# MezzanineConnectors.net
KiCad netlist of a schematic drawn in Altium Designer
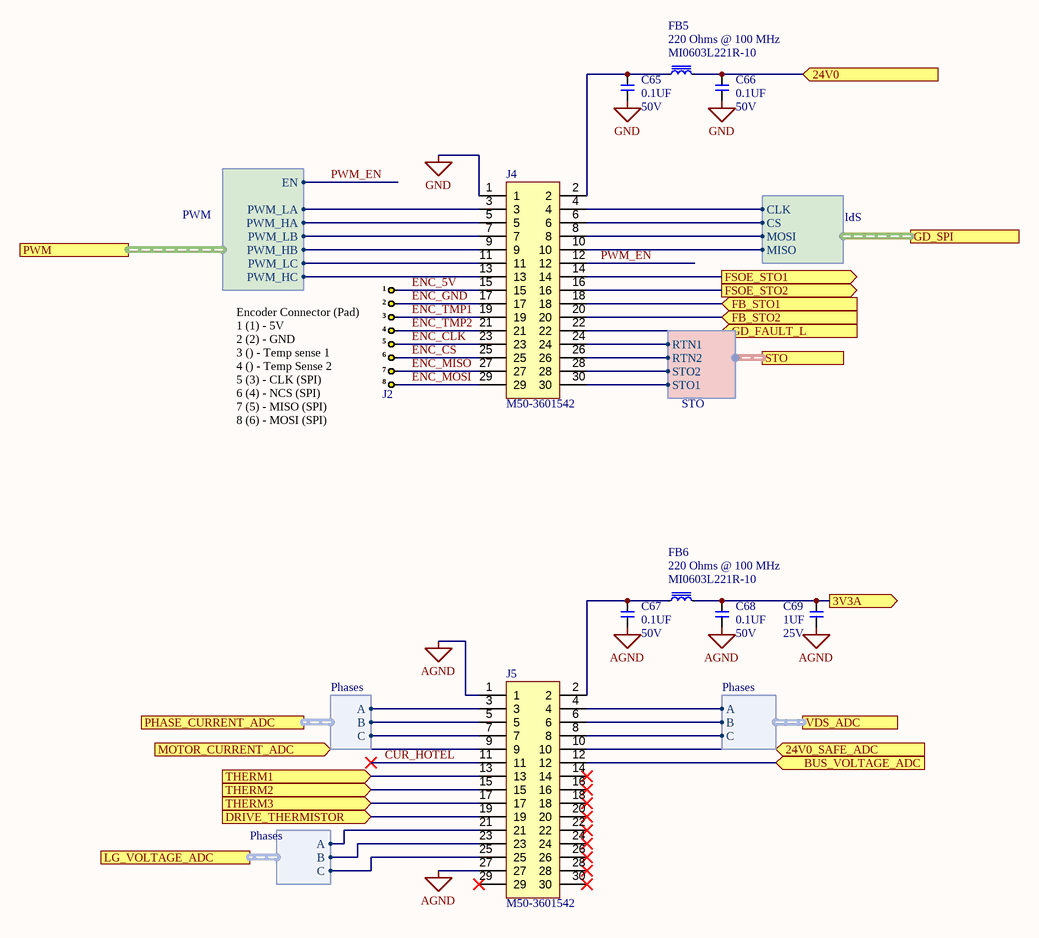
[diagram p0: MezzanineConnectors.SchDoc]

(export (version "E")
  (design (tool "Eeschema 10.0.6"))
  (components
    (comp (ref "C65")
      (value "0.1UF")
      (footprint "C0402")
      (description "CAP, CER, X5R, 0.1uF, 10%, 50V, 0402, 0.55mm")
      (fields (field (name "MFG") "YAGEO") (field (name "VOLTAGE") "50V") (field (name "TOLERANCE") "10%"))
      (libsource (lib "AltiumReleaseLibDB") (part "__Template_Cap"))
    )
    (comp (ref "C66")
      (value "0.1UF")
      (footprint "C0402")
      (description "CAP, CER, X5R, 0.1uF, 10%, 50V, 0402, 0.55mm")
      (fields (field (name "MFG") "YAGEO") (field (name "VOLTAGE") "50V") (field (name "TOLERANCE") "10%"))
      (libsource (lib "AltiumReleaseLibDB") (part "__Template_Cap"))
    )
    (comp (ref "C67")
      (value "0.1UF")
      (footprint "C0402")
      (description "CAP, CER, X5R, 0.1uF, 10%, 50V, 0402, 0.55mm")
      (fields (field (name "MFG") "YAGEO") (field (name "VOLTAGE") "50V") (field (name "TOLERANCE") "10%"))
      (libsource (lib "AltiumReleaseLibDB") (part "__Template_Cap"))
    )
    (comp (ref "C68")
      (value "0.1UF")
      (footprint "C0402")
      (description "CAP, CER, X5R, 0.1uF, 10%, 50V, 0402, 0.55mm")
      (fields (field (name "MFG") "YAGEO") (field (name "VOLTAGE") "50V") (field (name "TOLERANCE") "10%"))
      (libsource (lib "AltiumReleaseLibDB") (part "__Template_Cap"))
    )
    (comp (ref "C69")
      (value "1UF")
      (footprint "C0402")
      (description "CAP, CER, X5R, 1uF, 10%, 25V, 0402")
      (fields (field (name "MFG") "TDK") (field (name "VOLTAGE") "25V") (field (name "TOLERANCE") "10%"))
      (libsource (lib "AltiumReleaseLibDB") (part "__Template_Cap"))
    )
    (comp (ref "FB5")
      (value "220 Ohms @ 100 MHz")
      (footprint "INDC160X80X105L30N")
      (description "FERRITE BEAD 220 OHM 0603 1LN")
      (fields
        (field (name "MANUFACTURER") "Laird Technologies")
        (field (name "MANUFACTURER PART NUMBER") "MI0603L221R-10")
        (field (name "Comment") "LAIRD MI0603L221R-10")
      )
      (libsource (lib "Components") (part "FB"))
    )
    (comp (ref "FB6")
      (value "220 Ohms @ 100 MHz")
      (footprint "INDC160X80X105L30N")
      (description "FERRITE BEAD 220 OHM 0603 1LN")
      (fields
        (field (name "MANUFACTURER") "Laird Technologies")
        (field (name "MANUFACTURER PART NUMBER") "MI0603L221R-10")
        (field (name "Comment") "LAIRD MI0603L221R-10")
      )
      (libsource (lib "Components") (part "FB"))
    )
    (comp (ref "J2")
      (value "DIRECT_SOLDER_8_PIN")
      (footprint "8_PIN_DIRECT_25mil_1.5mm")
      (libsource (lib "MiscSch1") (part "DIRECT_SOLDER_8_PIN"))
    )
    (comp (ref "J4")
      (value "~")
      (footprint "HARWIN_M50-3601542")
      (description "CONN, HDR, UNSHRD, VERT, 2x15 P, 1.27MM PITCH, 5.33MM H, GOLD, SMD")
      (fields (field (name "MFG") "Harwin Inc.") (field (name "MFG P/N") "M50-3601542"))
      (libsource (lib "AltiumReleaseLibDB") (part "__Template_Connector_2X15"))
    )
    (comp (ref "J5")
      (value "~")
      (footprint "HARWIN_M50-3601542")
      (description "CONN, HDR, UNSHRD, VERT, 2x15 P, 1.27MM PITCH, 5.33MM H, GOLD, SMD")
      (fields (field (name "MFG") "Harwin Inc.") (field (name "MFG P/N") "M50-3601542"))
      (libsource (lib "AltiumReleaseLibDB") (part "__Template_Connector_2X15"))
    )
  )
  (nets
    (net (code "5") (name "/3V3A") (class "Default")
      (node (ref "C68") (pin "1") (pintype "passive"))
      (node (ref "C69") (pin "1") (pintype "passive"))
      (node (ref "FB6") (pin "2") (pintype "passive"))
    )
    (net (code "6") (name "/24V0") (class "Default")
      (node (ref "C66") (pin "1") (pintype "passive"))
      (node (ref "FB5") (pin "2") (pintype "passive"))
    )
    (net (code "7") (name "/24V0_SAFE_ADC") (class "Default")
      (node (ref "J5") (pin "10") (pinfunction "10_10") (pintype "passive"))
    )
    (net (code "8") (name "/BUS_VOLTAGE_ADC") (class "Default")
      (node (ref "J5") (pin "12") (pinfunction "12_12") (pintype "passive"))
    )
    (net (code "9") (name "/CLK") (class "Default")
      (node (ref "J4") (pin "4") (pinfunction "4_4") (pintype "passive"))
    )
    (net (code "10") (name "/CS") (class "Default")
      (node (ref "J4") (pin "6") (pinfunction "6_6") (pintype "passive"))
    )
    (net (code "11") (name "/CUR_HOTEL") (class "Default")
      (node (ref "J5") (pin "11") (pinfunction "11_11") (pintype "passive+no_connect"))
    )
    (net (code "12") (name "/DRIVE_THERMISTOR") (class "Default")
      (node (ref "J5") (pin "19") (pinfunction "19_19") (pintype "passive"))
    )
    (net (code "13") (name "/ENC_5V") (class "Default")
      (node (ref "J2") (pin "1") (pintype "passive"))
      (node (ref "J4") (pin "15") (pinfunction "15_15") (pintype "passive"))
    )
    (net (code "14") (name "/ENC_CLK") (class "Default")
      (node (ref "J2") (pin "5") (pintype "passive"))
      (node (ref "J4") (pin "23") (pinfunction "23_23") (pintype "passive"))
    )
    (net (code "15") (name "/ENC_CS") (class "Default")
      (node (ref "J2") (pin "6") (pintype "passive"))
      (node (ref "J4") (pin "25") (pinfunction "25_25") (pintype "passive"))
    )
    (net (code "16") (name "/ENC_GND") (class "Default")
      (node (ref "J2") (pin "2") (pintype "passive"))
      (node (ref "J4") (pin "17") (pinfunction "17_17") (pintype "passive"))
    )
    (net (code "17") (name "/ENC_MISO") (class "Default")
      (node (ref "J2") (pin "7") (pintype "passive"))
      (node (ref "J4") (pin "27") (pinfunction "27_27") (pintype "passive"))
    )
    (net (code "18") (name "/ENC_MOSI") (class "Default")
      (node (ref "J2") (pin "8") (pintype "passive"))
      (node (ref "J4") (pin "29") (pinfunction "29_29") (pintype "passive"))
    )
    (net (code "19") (name "/ENC_TMP1") (class "Default")
      (node (ref "J2") (pin "3") (pintype "passive"))
      (node (ref "J4") (pin "19") (pinfunction "19_19") (pintype "passive"))
    )
    (net (code "20") (name "/ENC_TMP2") (class "Default")
      (node (ref "J2") (pin "4") (pintype "passive"))
      (node (ref "J4") (pin "21") (pinfunction "21_21") (pintype "passive"))
    )
    (net (code "21") (name "/FB_STO1") (class "Default")
      (node (ref "J4") (pin "18") (pinfunction "18_18") (pintype "passive"))
    )
    (net (code "22") (name "/FB_STO2") (class "Default")
      (node (ref "J4") (pin "20") (pinfunction "20_20") (pintype "passive"))
    )
    (net (code "23") (name "/FSOE_STO1") (class "Default")
      (node (ref "J4") (pin "14") (pinfunction "14_14") (pintype "passive"))
    )
    (net (code "24") (name "/FSOE_STO2") (class "Default")
      (node (ref "J4") (pin "16") (pinfunction "16_16") (pintype "passive"))
    )
    (net (code "25") (name "/GD_FAULT_L") (class "Default")
      (node (ref "J4") (pin "22") (pinfunction "22_22") (pintype "passive"))
    )
    (net (code "26") (name "/MISO") (class "Default")
      (node (ref "J4") (pin "10") (pinfunction "10_10") (pintype "passive"))
    )
    (net (code "27") (name "/MOSI") (class "Default")
      (node (ref "J4") (pin "8") (pinfunction "8_8") (pintype "passive"))
    )
    (net (code "28") (name "/MOTOR_CURRENT_ADC") (class "Default")
      (node (ref "J5") (pin "9") (pinfunction "9_9") (pintype "passive"))
    )
    (net (code "29") (name "/PWM_EN") (class "Default")
      (node (ref "J4") (pin "12") (pinfunction "12_12") (pintype "passive"))
    )
    (net (code "30") (name "/PWM_HA") (class "Default")
      (node (ref "J4") (pin "5") (pinfunction "5_5") (pintype "passive"))
    )
    (net (code "31") (name "/PWM_HB") (class "Default")
      (node (ref "J4") (pin "9") (pinfunction "9_9") (pintype "passive"))
    )
    (net (code "32") (name "/PWM_HC") (class "Default")
      (node (ref "J4") (pin "13") (pinfunction "13_13") (pintype "passive"))
    )
    (net (code "33") (name "/PWM_LA") (class "Default")
      (node (ref "J4") (pin "3") (pinfunction "3_3") (pintype "passive"))
    )
    (net (code "34") (name "/PWM_LB") (class "Default")
      (node (ref "J4") (pin "7") (pinfunction "7_7") (pintype "passive"))
    )
    (net (code "35") (name "/PWM_LC") (class "Default")
      (node (ref "J4") (pin "11") (pinfunction "11_11") (pintype "passive"))
    )
    (net (code "36") (name "/RTN1") (class "Default")
      (node (ref "J4") (pin "24") (pinfunction "24_24") (pintype "passive"))
    )
    (net (code "37") (name "/RTN2") (class "Default")
      (node (ref "J4") (pin "26") (pinfunction "26_26") (pintype "passive"))
    )
    (net (code "38") (name "/STO1") (class "Default")
      (node (ref "J4") (pin "30") (pinfunction "30_30") (pintype "passive"))
    )
    (net (code "39") (name "/STO2") (class "Default")
      (node (ref "J4") (pin "28") (pinfunction "28_28") (pintype "passive"))
    )
    (net (code "40") (name "/THERM1") (class "Default")
      (node (ref "J5") (pin "13") (pinfunction "13_13") (pintype "passive"))
    )
    (net (code "41") (name "/THERM2") (class "Default")
      (node (ref "J5") (pin "15") (pinfunction "15_15") (pintype "passive"))
    )
    (net (code "42") (name "/THERM3") (class "Default")
      (node (ref "J5") (pin "17") (pinfunction "17_17") (pintype "passive"))
    )
    (net (code "47") (name "AGND") (class "Default")
      (node (ref "C67") (pin "2") (pintype "passive"))
      (node (ref "C68") (pin "2") (pintype "passive"))
      (node (ref "C69") (pin "2") (pintype "passive"))
      (node (ref "J5") (pin "1") (pinfunction "1_1") (pintype "passive"))
      (node (ref "J5") (pin "27") (pinfunction "27_27") (pintype "passive"))
    )
    (net (code "48") (name "GND") (class "Default")
      (node (ref "C65") (pin "2") (pintype "passive"))
      (node (ref "C66") (pin "2") (pintype "passive"))
      (node (ref "J4") (pin "1") (pinfunction "1_1") (pintype "passive"))
    )
    (net (code "49") (name "Net-(C65-Pad1)") (class "Default")
      (node (ref "C65") (pin "1") (pintype "passive"))
      (node (ref "FB5") (pin "1") (pintype "passive"))
      (node (ref "J4") (pin "2") (pinfunction "2_2") (pintype "passive"))
    )
    (net (code "50") (name "Net-(C67-Pad1)") (class "Default")
      (node (ref "C67") (pin "1") (pintype "passive"))
      (node (ref "FB6") (pin "1") (pintype "passive"))
      (node (ref "J5") (pin "2") (pinfunction "2_2") (pintype "passive"))
    )
    (net (code "51") (name "unconnected-(J5-Pad3)") (class "Default")
      (node (ref "J5") (pin "3") (pinfunction "3_3") (pintype "passive"))
    )
    (net (code "52") (name "unconnected-(J5-Pad4)") (class "Default")
      (node (ref "J5") (pin "4") (pinfunction "4_4") (pintype "passive"))
    )
    (net (code "53") (name "unconnected-(J5-Pad5)") (class "Default")
      (node (ref "J5") (pin "5") (pinfunction "5_5") (pintype "passive"))
    )
    (net (code "54") (name "unconnected-(J5-Pad6)") (class "Default")
      (node (ref "J5") (pin "6") (pinfunction "6_6") (pintype "passive"))
    )
    (net (code "55") (name "unconnected-(J5-Pad7)") (class "Default")
      (node (ref "J5") (pin "7") (pinfunction "7_7") (pintype "passive"))
    )
    (net (code "56") (name "unconnected-(J5-Pad8)") (class "Default")
      (node (ref "J5") (pin "8") (pinfunction "8_8") (pintype "passive"))
    )
    (net (code "57") (name "unconnected-(J5-Pad14)") (class "Default")
      (node (ref "J5") (pin "14") (pinfunction "14_14") (pintype "passive+no_connect"))
    )
    (net (code "58") (name "unconnected-(J5-Pad16)") (class "Default")
      (node (ref "J5") (pin "16") (pinfunction "16_16") (pintype "passive+no_connect"))
    )
    (net (code "59") (name "unconnected-(J5-Pad18)") (class "Default")
      (node (ref "J5") (pin "18") (pinfunction "18_18") (pintype "passive+no_connect"))
    )
    (net (code "60") (name "unconnected-(J5-Pad20)") (class "Default")
      (node (ref "J5") (pin "20") (pinfunction "20_20") (pintype "passive+no_connect"))
    )
    (net (code "61") (name "unconnected-(J5-Pad21)") (class "Default")
      (node (ref "J5") (pin "21") (pinfunction "21_21") (pintype "passive"))
    )
    (net (code "62") (name "unconnected-(J5-Pad22)") (class "Default")
      (node (ref "J5") (pin "22") (pinfunction "22_22") (pintype "passive+no_connect"))
    )
    (net (code "63") (name "unconnected-(J5-Pad23)") (class "Default")
      (node (ref "J5") (pin "23") (pinfunction "23_23") (pintype "passive"))
    )
    (net (code "64") (name "unconnected-(J5-Pad24)") (class "Default")
      (node (ref "J5") (pin "24") (pinfunction "24_24") (pintype "passive+no_connect"))
    )
    (net (code "65") (name "unconnected-(J5-Pad25)") (class "Default")
      (node (ref "J5") (pin "25") (pinfunction "25_25") (pintype "passive"))
    )
    (net (code "66") (name "unconnected-(J5-Pad26)") (class "Default")
      (node (ref "J5") (pin "26") (pinfunction "26_26") (pintype "passive+no_connect"))
    )
    (net (code "67") (name "unconnected-(J5-Pad28)") (class "Default")
      (node (ref "J5") (pin "28") (pinfunction "28_28") (pintype "passive+no_connect"))
    )
    (net (code "68") (name "unconnected-(J5-Pad29)") (class "Default")
      (node (ref "J5") (pin "29") (pinfunction "29_29") (pintype "passive+no_connect"))
    )
    (net (code "69") (name "unconnected-(J5-Pad30)") (class "Default")
      (node (ref "J5") (pin "30") (pinfunction "30_30") (pintype "passive+no_connect"))
    )
  )
)
